# optoswitch.net
KiCad netlist of a schematic drawn in EAGLE
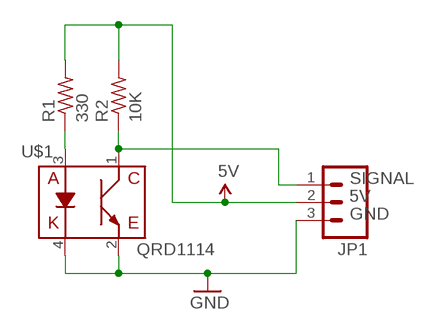
[diagram p0: schematic, sheet 1]

(export (version "E")
  (design (tool "Eeschema 10.0.6"))
  (components
    (comp (ref "JP1")
      (value "M03POLAR")
      (footprint "eagle-import:MOLEX-1X3")
      (libsource (lib "eagle-import") (part "M03POLAR"))
    )
    (comp (ref "R1")
      (value "330")
      (footprint "eagle-import:R2512")
      (libsource (lib "eagle-import") (part "R-US_R2512"))
    )
    (comp (ref "R2")
      (value "10K")
      (footprint "eagle-import:R2512")
      (libsource (lib "eagle-import") (part "R-US_R2512"))
    )
    (comp (ref "U$1")
      (value "QRD1114")
      (footprint "eagle-import:QRD1114")
      (libsource (lib "eagle-import") (part "QRD1114"))
    )
  )
  (nets
    (net (code "1") (name "/SIGNAL") (class "Default")
      (node (ref "JP1") (pin "1") (pinfunction "1_1") (pintype "passive"))
      (node (ref "R2") (pin "1") (pinfunction "1_1") (pintype "passive"))
      (node (ref "U$1") (pin "1") (pinfunction "E_1") (pintype "bidirectional"))
    )
    (net (code "2") (name "5V") (class "Default")
      (node (ref "JP1") (pin "2") (pinfunction "2_2") (pintype "passive"))
      (node (ref "R1") (pin "2") (pinfunction "2_2") (pintype "passive"))
      (node (ref "R2") (pin "2") (pinfunction "2_2") (pintype "passive"))
    )
    (net (code "3") (name "GND") (class "Default")
      (node (ref "JP1") (pin "3") (pinfunction "3_3") (pintype "passive"))
      (node (ref "U$1") (pin "2") (pinfunction "C_2") (pintype "bidirectional"))
      (node (ref "U$1") (pin "4") (pinfunction "K_4") (pintype "bidirectional"))
    )
    (net (code "4") (name "Net-(U$1-A)") (class "Default")
      (node (ref "R1") (pin "1") (pinfunction "1_1") (pintype "passive"))
      (node (ref "U$1") (pin "3") (pinfunction "A_3") (pintype "bidirectional"))
    )
  )
)
